# OV7670_headers.net
KiCad netlist of a schematic drawn in Altium Designer
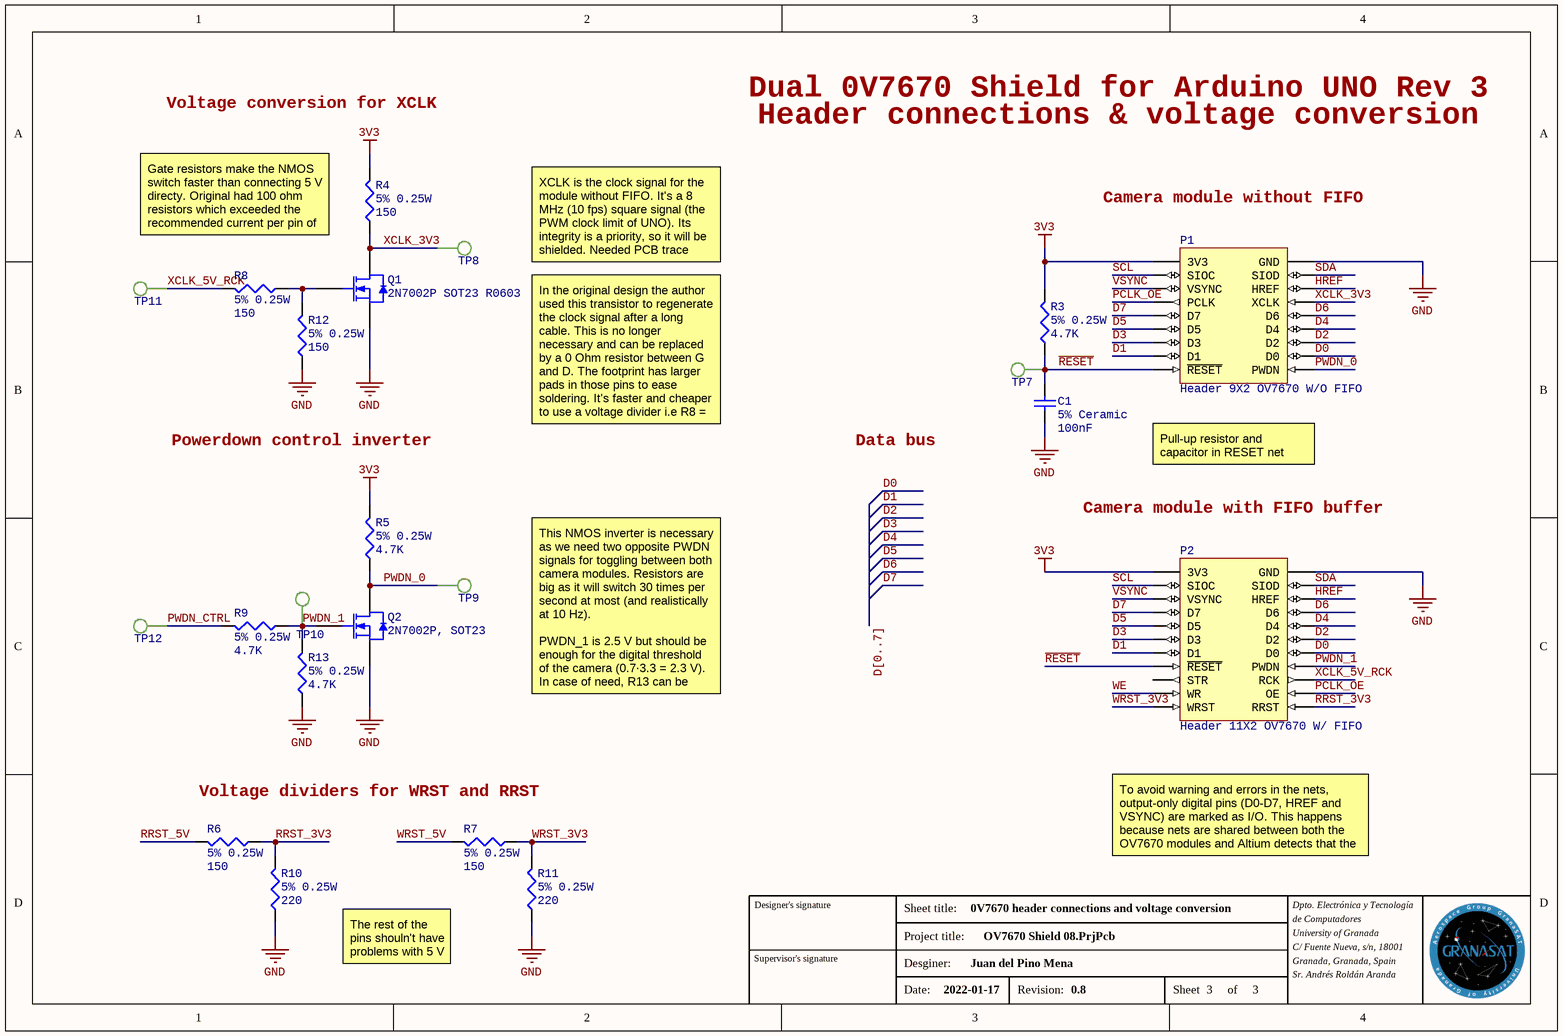
[diagram p0: OV7670_headers.SchDoc]

(export (version "E")
  (design (tool "Eeschema 10.0.6"))
  (components
    (comp (ref "C1")
      (value "5% Ceramic")
      (footprint "0805 CAP")
      (description "SMD Ceramic Capacitor 100nF 5% 0805")
      (fields (field (name "ALTIUM_VALUE") "100nF") (field (name "PUBLISHER") "Altium Limited"))
      (libsource (lib "shield_SCH_LIB") (part "Cap100nF"))
    )
    (comp (ref "P1")
      (value "Header 9X2 OV7670 W/O FIFO")
      (footprint "9x2 PIN HEADER")
      (description "Header, 9-Pin, Dual row. Pinout of OV7670 module without FIFO buffer.")
      (fields (field (name "PUBLISHER") "Altium Limited"))
      (libsource (lib "shield_SCH_LIB") (part "Header 9X2 OV7670 W/O FIFO"))
    )
    (comp (ref "P2")
      (value "Header 11X2 OV7670 W/ FIFO")
      (footprint "11x2 PIN HEADER")
      (description "Header, 11-Pin, Dual row. Pinout of OV7670 module with FIFO buffer.")
      (fields (field (name "PUBLISHER") "Altium Limited"))
      (libsource (lib "shield_SCH_LIB") (part "Header 11X2 OV7670 W/ FIFO"))
    )
    (comp (ref "Q1")
      (value "2N7002P SOT23 R0603")
      (footprint "2N7002P SOT23 WITH LARGE G,D PADS")
      (description "N-Channel MOSFET 2N7002P SOT23\r\nversion with footprint compatible with 0 Ohm 0603 resistor")
      (fields (field (name "PUBLISHER") "Altium Limited"))
      (libsource (lib "shield_SCH_LIB") (part "2N7002P (0Ohm)"))
    )
    (comp (ref "Q2")
      (value "2N7002P, SOT23")
      (footprint "2N7002P SOT23")
      (description "N-Channel MOSFET 2N7002P SOT23")
      (fields (field (name "PUBLISHER") "Altium Limited"))
      (libsource (lib "shield_SCH_LIB") (part "2N7002P"))
    )
    (comp (ref "R3")
      (value "5% 0.25W")
      (footprint "0603 RES")
      (description "SMD Resistor 4.7 KOhm 5% 0.1W 0603")
      (fields (field (name "ALTIUM_VALUE") "4.7K") (field (name "PUBLISHER") "Altium Limited"))
      (libsource (lib "shield_SCH_LIB") (part "Res4K7"))
    )
    (comp (ref "R4")
      (value "5% 0.25W")
      (footprint "0603 RES")
      (description "SMD Resistor 150 Ohm 5% 0.25W 0603")
      (fields (field (name "ALTIUM_VALUE") "150") (field (name "PUBLISHER") "Altium Limited"))
      (libsource (lib "shield_SCH_LIB") (part "Res150R"))
    )
    (comp (ref "R5")
      (value "5% 0.25W")
      (footprint "0603 RES")
      (description "SMD Resistor 4.7 KOhm 5% 0.1W 0603")
      (fields (field (name "ALTIUM_VALUE") "4.7K") (field (name "PUBLISHER") "Altium Limited"))
      (libsource (lib "shield_SCH_LIB") (part "Res4K7"))
    )
    (comp (ref "R6")
      (value "5% 0.25W")
      (footprint "0603 RES")
      (description "SMD Resistor 150 Ohm 5% 0.25W 0603")
      (fields (field (name "ALTIUM_VALUE") "150") (field (name "PUBLISHER") "Altium Limited"))
      (libsource (lib "shield_SCH_LIB") (part "Res150R"))
    )
    (comp (ref "R7")
      (value "5% 0.25W")
      (footprint "0603 RES")
      (description "SMD Resistor 150 Ohm 5% 0.25W 0603")
      (fields (field (name "ALTIUM_VALUE") "150") (field (name "PUBLISHER") "Altium Limited"))
      (libsource (lib "shield_SCH_LIB") (part "Res150R"))
    )
    (comp (ref "R8")
      (value "5% 0.25W")
      (footprint "0603 RES")
      (description "SMD Resistor 150 Ohm 5% 0.25W 0603")
      (fields (field (name "ALTIUM_VALUE") "150") (field (name "PUBLISHER") "Altium Limited"))
      (libsource (lib "shield_SCH_LIB") (part "Res150R"))
    )
    (comp (ref "R9")
      (value "5% 0.25W")
      (footprint "0603 RES")
      (description "SMD Resistor 4.7 KOhm 5% 0.1W 0603")
      (fields (field (name "ALTIUM_VALUE") "4.7K") (field (name "PUBLISHER") "Altium Limited"))
      (libsource (lib "shield_SCH_LIB") (part "Res4K7"))
    )
    (comp (ref "R10")
      (value "5% 0.25W")
      (footprint "0603 RES")
      (description "SMD Resistor 220 Ohm 5% 0.25W 0603")
      (fields (field (name "ALTIUM_VALUE") "220") (field (name "PUBLISHER") "Altium Limited"))
      (libsource (lib "shield_SCH_LIB") (part "Res220R"))
    )
    (comp (ref "R11")
      (value "5% 0.25W")
      (footprint "0603 RES")
      (description "SMD Resistor 220 Ohm 5% 0.25W 0603")
      (fields (field (name "ALTIUM_VALUE") "220") (field (name "PUBLISHER") "Altium Limited"))
      (libsource (lib "shield_SCH_LIB") (part "Res220R"))
    )
    (comp (ref "R12")
      (value "5% 0.25W")
      (footprint "0603 RES")
      (description "SMD Resistor 150 Ohm 5% 0.25W 0603")
      (fields (field (name "ALTIUM_VALUE") "150") (field (name "PUBLISHER") "Altium Limited"))
      (libsource (lib "shield_SCH_LIB") (part "Res150R"))
    )
    (comp (ref "R13")
      (value "5% 0.25W")
      (footprint "0603 RES")
      (description "SMD Resistor 4.7 KOhm 5% 0.1W 0603")
      (fields (field (name "ALTIUM_VALUE") "4.7K") (field (name "PUBLISHER") "Altium Limited"))
      (libsource (lib "shield_SCH_LIB") (part "Res4K7"))
    )
    (comp (ref "TP7")
      (value "Test Point Pad")
      (footprint "TEST POINT PAD")
      (description "Test point - PCB Pad type.")
      (libsource (lib "shield_SCH_LIB") (part "Test Point Pad"))
    )
    (comp (ref "TP8")
      (value "Test Point Pad")
      (footprint "TEST POINT PAD")
      (description "Test point - PCB Pad type.")
      (libsource (lib "shield_SCH_LIB") (part "Test Point Pad"))
    )
    (comp (ref "TP9")
      (value "Test Point Pad")
      (footprint "TEST POINT PAD")
      (description "Test point - PCB Pad type.")
      (libsource (lib "shield_SCH_LIB") (part "Test Point Pad"))
    )
    (comp (ref "TP10")
      (value "Test Point Pad")
      (footprint "TEST POINT PAD")
      (description "Test point - PCB Pad type.")
      (libsource (lib "shield_SCH_LIB") (part "Test Point Pad"))
    )
    (comp (ref "TP11")
      (value "Test Point Pad")
      (footprint "TEST POINT PAD")
      (description "Test point - PCB Pad type.")
      (libsource (lib "shield_SCH_LIB") (part "Test Point Pad"))
    )
    (comp (ref "TP12")
      (value "Test Point Pad")
      (footprint "TEST POINT PAD")
      (description "Test point - PCB Pad type.")
      (libsource (lib "shield_SCH_LIB") (part "Test Point Pad"))
    )
  )
  (nets
    (net (code "1") (name "/D0") (class "Default")
      (node (ref "P1") (pin "16") (pinfunction "D0_16") (pintype "bidirectional"))
      (node (ref "P2") (pin "14") (pinfunction "D0_14") (pintype "bidirectional"))
    )
    (net (code "2") (name "/D1") (class "Default")
      (node (ref "P1") (pin "15") (pinfunction "D1_15") (pintype "bidirectional"))
      (node (ref "P2") (pin "13") (pinfunction "D1_13") (pintype "bidirectional"))
    )
    (net (code "3") (name "/D2") (class "Default")
      (node (ref "P1") (pin "14") (pinfunction "D2_14") (pintype "bidirectional"))
      (node (ref "P2") (pin "12") (pinfunction "D2_12") (pintype "bidirectional"))
    )
    (net (code "4") (name "/D3") (class "Default")
      (node (ref "P1") (pin "13") (pinfunction "D3_13") (pintype "bidirectional"))
      (node (ref "P2") (pin "11") (pinfunction "D3_11") (pintype "bidirectional"))
    )
    (net (code "5") (name "/D4") (class "Default")
      (node (ref "P1") (pin "12") (pinfunction "D4_12") (pintype "bidirectional"))
      (node (ref "P2") (pin "10") (pinfunction "D4_10") (pintype "bidirectional"))
    )
    (net (code "6") (name "/D5") (class "Default")
      (node (ref "P1") (pin "11") (pinfunction "D5_11") (pintype "bidirectional"))
      (node (ref "P2") (pin "9") (pinfunction "D5_9") (pintype "bidirectional"))
    )
    (net (code "7") (name "/D6") (class "Default")
      (node (ref "P1") (pin "10") (pinfunction "D6_10") (pintype "bidirectional"))
      (node (ref "P2") (pin "8") (pinfunction "D6_8") (pintype "bidirectional"))
    )
    (net (code "8") (name "/D7") (class "Default")
      (node (ref "P1") (pin "9") (pinfunction "D7_9") (pintype "bidirectional"))
      (node (ref "P2") (pin "7") (pinfunction "D7_7") (pintype "bidirectional"))
    )
    (net (code "10") (name "/HREF") (class "Default")
      (node (ref "P1") (pin "6") (pinfunction "HREF_6") (pintype "bidirectional"))
      (node (ref "P2") (pin "6") (pinfunction "HREF_6") (pintype "bidirectional"))
    )
    (net (code "11") (name "/PCLK_OE") (class "Default")
      (node (ref "P1") (pin "7") (pinfunction "PCLK_7") (pintype "output"))
      (node (ref "P2") (pin "20") (pinfunction "OE_20") (pintype "input"))
    )
    (net (code "12") (name "/PWDN_0") (class "Default")
      (node (ref "P1") (pin "18") (pinfunction "PWDN_18") (pintype "input"))
      (node (ref "Q2") (pin "2") (pinfunction "D_2") (pintype "passive"))
      (node (ref "R5") (pin "1") (pinfunction "1_1") (pintype "passive"))
      (node (ref "TP9") (pin "1") (pinfunction "1_1") (pintype "passive"))
    )
    (net (code "13") (name "/PWDN_1") (class "Default")
      (node (ref "P2") (pin "16") (pinfunction "PWDN_16") (pintype "input"))
      (node (ref "Q2") (pin "1") (pinfunction "G_1") (pintype "passive"))
      (node (ref "R13") (pin "2") (pinfunction "2_2") (pintype "passive"))
      (node (ref "R9") (pin "1") (pinfunction "1_1") (pintype "passive"))
      (node (ref "TP10") (pin "1") (pinfunction "1_1") (pintype "passive"))
    )
    (net (code "14") (name "/PWDN_CTRL") (class "Default")
      (node (ref "R9") (pin "2") (pinfunction "2_2") (pintype "passive"))
      (node (ref "TP12") (pin "1") (pinfunction "1_1") (pintype "passive"))
    )
    (net (code "15") (name "/RRST_3V3") (class "Default")
      (node (ref "P2") (pin "22") (pinfunction "RRST_22") (pintype "input"))
      (node (ref "R10") (pin "2") (pinfunction "2_2") (pintype "passive"))
      (node (ref "R6") (pin "1") (pinfunction "1_1") (pintype "passive"))
    )
    (net (code "16") (name "/RRST_5V") (class "Default")
      (node (ref "R6") (pin "2") (pinfunction "2_2") (pintype "passive"))
    )
    (net (code "17") (name "/SCL") (class "Default")
      (node (ref "P1") (pin "3") (pinfunction "SIOC_3") (pintype "bidirectional"))
      (node (ref "P2") (pin "3") (pinfunction "SIOC_3") (pintype "bidirectional"))
    )
    (net (code "18") (name "/SDA") (class "Default")
      (node (ref "P1") (pin "4") (pinfunction "SIOD_4") (pintype "bidirectional"))
      (node (ref "P2") (pin "4") (pinfunction "SIOD_4") (pintype "bidirectional"))
    )
    (net (code "19") (name "/VSYNC") (class "Default")
      (node (ref "P1") (pin "5") (pinfunction "VSYNC_5") (pintype "bidirectional"))
      (node (ref "P2") (pin "5") (pinfunction "VSYNC_5") (pintype "bidirectional"))
    )
    (net (code "20") (name "/WE") (class "Default")
      (node (ref "P2") (pin "19") (pinfunction "WR_19") (pintype "input"))
    )
    (net (code "21") (name "/WRST_3V3") (class "Default")
      (node (ref "P2") (pin "21") (pinfunction "WRST_21") (pintype "input"))
      (node (ref "R11") (pin "2") (pinfunction "2_2") (pintype "passive"))
      (node (ref "R7") (pin "1") (pinfunction "1_1") (pintype "passive"))
    )
    (net (code "22") (name "/WRST_5V") (class "Default")
      (node (ref "R7") (pin "2") (pinfunction "2_2") (pintype "passive"))
    )
    (net (code "23") (name "/XCLK_3V3") (class "Default")
      (node (ref "P1") (pin "8") (pinfunction "XCLK_8") (pintype "input"))
      (node (ref "Q1") (pin "2") (pinfunction "D_2") (pintype "passive"))
      (node (ref "R4") (pin "1") (pinfunction "1_1") (pintype "passive"))
      (node (ref "TP8") (pin "1") (pinfunction "1_1") (pintype "passive"))
    )
    (net (code "24") (name "/XCLK_5V_RCK") (class "Default")
      (node (ref "P2") (pin "18") (pinfunction "RCK_18") (pintype "output"))
      (node (ref "R8") (pin "2") (pinfunction "2_2") (pintype "passive"))
      (node (ref "TP11") (pin "1") (pinfunction "1_1") (pintype "passive"))
    )
    (net (code "25") (name "/~{RESET}") (class "Default")
      (node (ref "C1") (pin "2") (pinfunction "2_2") (pintype "passive"))
      (node (ref "P1") (pin "17") (pinfunction "~{RESET}_17") (pintype "input"))
      (node (ref "P2") (pin "15") (pinfunction "~{RESET}_15") (pintype "input"))
      (node (ref "R3") (pin "1") (pinfunction "1_1") (pintype "passive"))
      (node (ref "TP7") (pin "1") (pinfunction "1_1") (pintype "passive"))
    )
    (net (code "26") (name "3V3") (class "Default")
      (node (ref "P1") (pin "1") (pinfunction "3V3_1") (pintype "power_in"))
      (node (ref "P2") (pin "1") (pinfunction "3V3_1") (pintype "power_in"))
      (node (ref "R3") (pin "2") (pinfunction "2_2") (pintype "passive"))
      (node (ref "R4") (pin "2") (pinfunction "2_2") (pintype "passive"))
      (node (ref "R5") (pin "2") (pinfunction "2_2") (pintype "passive"))
    )
    (net (code "27") (name "GND") (class "Default")
      (node (ref "C1") (pin "1") (pinfunction "1_1") (pintype "passive"))
      (node (ref "P1") (pin "2") (pinfunction "GND_2") (pintype "power_in"))
      (node (ref "P2") (pin "2") (pinfunction "GND_2") (pintype "passive"))
      (node (ref "Q1") (pin "3") (pinfunction "S_3") (pintype "passive"))
      (node (ref "Q2") (pin "3") (pinfunction "S_3") (pintype "passive"))
      (node (ref "R10") (pin "1") (pinfunction "1_1") (pintype "passive"))
      (node (ref "R11") (pin "1") (pinfunction "1_1") (pintype "passive"))
      (node (ref "R12") (pin "1") (pinfunction "1_1") (pintype "passive"))
      (node (ref "R13") (pin "1") (pinfunction "1_1") (pintype "passive"))
    )
    (net (code "28") (name "Net-(Q1-G)") (class "Default")
      (node (ref "Q1") (pin "1") (pinfunction "G_1") (pintype "passive"))
      (node (ref "R12") (pin "2") (pinfunction "2_2") (pintype "passive"))
      (node (ref "R8") (pin "1") (pinfunction "1_1") (pintype "passive"))
    )
    (net (code "29") (name "unconnected-(P2-STR-Pad17)") (class "Default")
      (node (ref "P2") (pin "17") (pinfunction "STR_17") (pintype "output"))
    )
  )
)
